# NeoDigito_Mini_V2.net
KiCad netlist of a schematic drawn in EAGLE
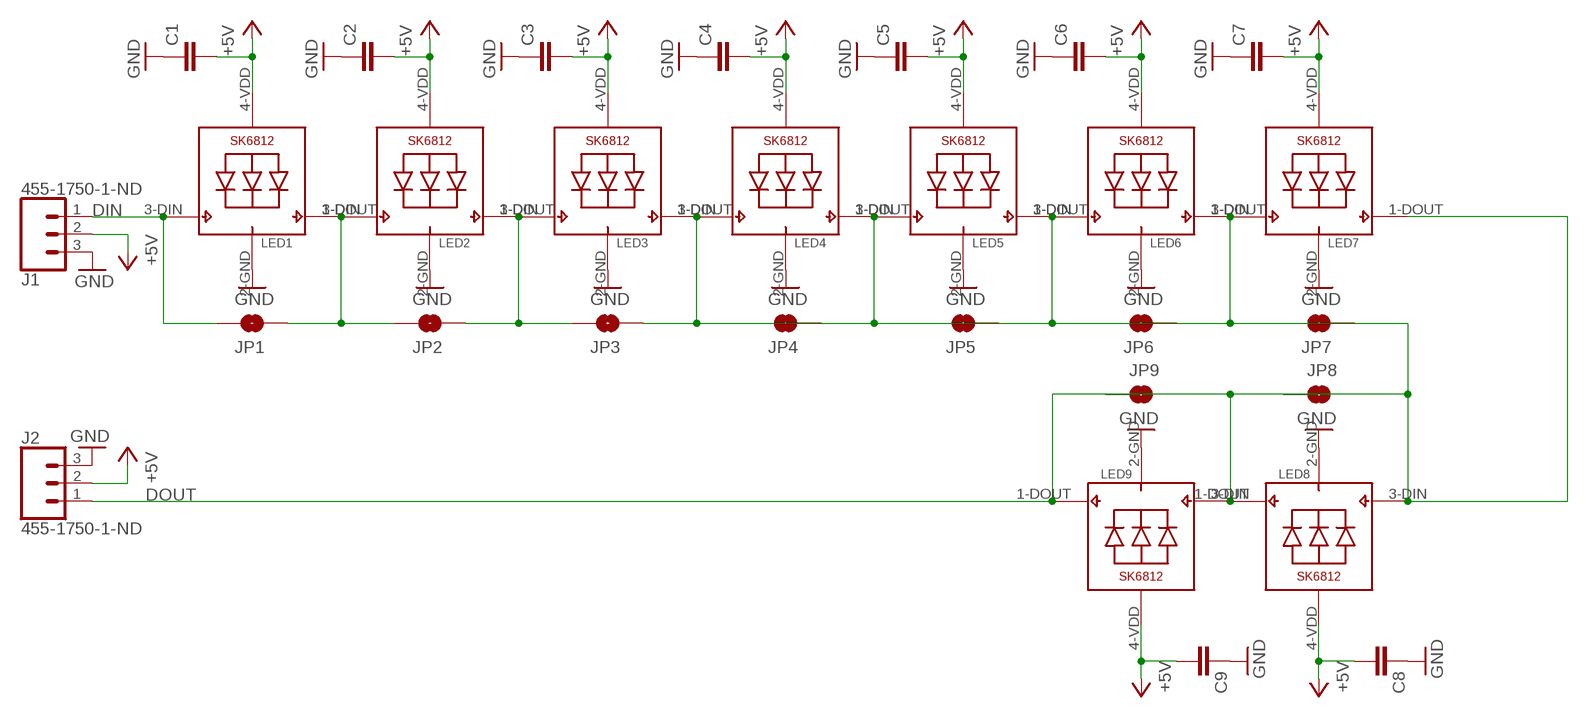
[diagram p0: schematic, sheet 1]

(export (version "E")
  (design (tool "Eeschema 10.0.6"))
  (components
    (comp (ref "C1")
      (value "C-EUC0805")
      (footprint "eagle-import:C0805")
      (libsource (lib "eagle-import") (part "C-EUC0805"))
    )
    (comp (ref "C2")
      (value "C-EUC0805")
      (footprint "eagle-import:C0805")
      (libsource (lib "eagle-import") (part "C-EUC0805"))
    )
    (comp (ref "C3")
      (value "C-EUC0805")
      (footprint "eagle-import:C0805")
      (libsource (lib "eagle-import") (part "C-EUC0805"))
    )
    (comp (ref "C4")
      (value "C-EUC0805")
      (footprint "eagle-import:C0805")
      (libsource (lib "eagle-import") (part "C-EUC0805"))
    )
    (comp (ref "C5")
      (value "C-EUC0805")
      (footprint "eagle-import:C0805")
      (libsource (lib "eagle-import") (part "C-EUC0805"))
    )
    (comp (ref "C6")
      (value "C-EUC0805")
      (footprint "eagle-import:C0805")
      (libsource (lib "eagle-import") (part "C-EUC0805"))
    )
    (comp (ref "C7")
      (value "C-EUC0805")
      (footprint "eagle-import:C0805")
      (libsource (lib "eagle-import") (part "C-EUC0805"))
    )
    (comp (ref "C8")
      (value "C-EUC0805")
      (footprint "eagle-import:C0805")
      (libsource (lib "eagle-import") (part "C-EUC0805"))
    )
    (comp (ref "C9")
      (value "C-EUC0805")
      (footprint "eagle-import:C0805")
      (libsource (lib "eagle-import") (part "C-EUC0805"))
    )
    (comp (ref "J1")
      (value "455-1750-1-ND")
      (footprint "eagle-import:1X03")
      (libsource (lib "eagle-import") (part "CONN_03"))
    )
    (comp (ref "J2")
      (value "455-1750-1-ND")
      (footprint "eagle-import:1X03")
      (libsource (lib "eagle-import") (part "CONN_03"))
    )
    (comp (ref "JP1")
      (value "JUMPER-SMT_2_NO_SILK")
      (footprint "eagle-import:SMT-JUMPER_2_NO_SILK")
      (libsource (lib "eagle-import") (part "JUMPER-SMT_2_NO_SILK"))
    )
    (comp (ref "JP2")
      (value "JUMPER-SMT_2_NO_SILK")
      (footprint "eagle-import:SMT-JUMPER_2_NO_SILK")
      (libsource (lib "eagle-import") (part "JUMPER-SMT_2_NO_SILK"))
    )
    (comp (ref "JP3")
      (value "JUMPER-SMT_2_NO_SILK")
      (footprint "eagle-import:SMT-JUMPER_2_NO_SILK")
      (libsource (lib "eagle-import") (part "JUMPER-SMT_2_NO_SILK"))
    )
    (comp (ref "JP4")
      (value "JUMPER-SMT_2_NO_SILK")
      (footprint "eagle-import:SMT-JUMPER_2_NO_SILK")
      (libsource (lib "eagle-import") (part "JUMPER-SMT_2_NO_SILK"))
    )
    (comp (ref "JP5")
      (value "JUMPER-SMT_2_NO_SILK")
      (footprint "eagle-import:SMT-JUMPER_2_NO_SILK")
      (libsource (lib "eagle-import") (part "JUMPER-SMT_2_NO_SILK"))
    )
    (comp (ref "JP6")
      (value "JUMPER-SMT_2_NO_SILK")
      (footprint "eagle-import:SMT-JUMPER_2_NO_SILK")
      (libsource (lib "eagle-import") (part "JUMPER-SMT_2_NO_SILK"))
    )
    (comp (ref "JP7")
      (value "JUMPER-SMT_2_NO_SILK")
      (footprint "eagle-import:SMT-JUMPER_2_NO_SILK")
      (libsource (lib "eagle-import") (part "JUMPER-SMT_2_NO_SILK"))
    )
    (comp (ref "JP8")
      (value "JUMPER-SMT_2_NO_SILK")
      (footprint "eagle-import:SMT-JUMPER_2_NO_SILK")
      (libsource (lib "eagle-import") (part "JUMPER-SMT_2_NO_SILK"))
    )
    (comp (ref "JP9")
      (value "JUMPER-SMT_2_NO_SILK")
      (footprint "eagle-import:SMT-JUMPER_2_NO_SILK")
      (libsource (lib "eagle-import") (part "JUMPER-SMT_2_NO_SILK"))
    )
    (comp (ref "LED1")
      (value "SK6812_3535")
      (footprint "eagle-import:LED3535")
      (libsource (lib "eagle-import") (part "SK6812_3535"))
    )
    (comp (ref "LED2")
      (value "SK6812_3535")
      (footprint "eagle-import:LED3535")
      (libsource (lib "eagle-import") (part "SK6812_3535"))
    )
    (comp (ref "LED3")
      (value "SK6812_3535")
      (footprint "eagle-import:LED3535")
      (libsource (lib "eagle-import") (part "SK6812_3535"))
    )
    (comp (ref "LED4")
      (value "SK6812_3535")
      (footprint "eagle-import:LED3535")
      (libsource (lib "eagle-import") (part "SK6812_3535"))
    )
    (comp (ref "LED5")
      (value "SK6812_3535")
      (footprint "eagle-import:LED3535")
      (libsource (lib "eagle-import") (part "SK6812_3535"))
    )
    (comp (ref "LED6")
      (value "SK6812_3535")
      (footprint "eagle-import:LED3535")
      (libsource (lib "eagle-import") (part "SK6812_3535"))
    )
    (comp (ref "LED7")
      (value "SK6812_3535")
      (footprint "eagle-import:LED3535")
      (libsource (lib "eagle-import") (part "SK6812_3535"))
    )
    (comp (ref "LED8")
      (value "SK6812_3535")
      (footprint "eagle-import:LED3535")
      (libsource (lib "eagle-import") (part "SK6812_3535"))
    )
    (comp (ref "LED9")
      (value "SK6812_3535")
      (footprint "eagle-import:LED3535")
      (libsource (lib "eagle-import") (part "SK6812_3535"))
    )
  )
  (nets
    (net (code "1") (name "+5V") (class "Default")
      (node (ref "C1") (pin "2") (pinfunction "2_2") (pintype "passive"))
      (node (ref "C2") (pin "2") (pinfunction "2_2") (pintype "passive"))
      (node (ref "C3") (pin "2") (pinfunction "2_2") (pintype "passive"))
      (node (ref "C4") (pin "2") (pinfunction "2_2") (pintype "passive"))
      (node (ref "C5") (pin "2") (pinfunction "2_2") (pintype "passive"))
      (node (ref "C6") (pin "2") (pinfunction "2_2") (pintype "passive"))
      (node (ref "C7") (pin "2") (pinfunction "2_2") (pintype "passive"))
      (node (ref "C8") (pin "2") (pinfunction "2_2") (pintype "passive"))
      (node (ref "C9") (pin "2") (pinfunction "2_2") (pintype "passive"))
      (node (ref "J1") (pin "2") (pinfunction "2_2") (pintype "passive"))
      (node (ref "J2") (pin "2") (pinfunction "2_2") (pintype "passive"))
      (node (ref "LED1") (pin "4-VDD") (pinfunction "VDD_4-VDD") (pintype "power_in"))
      (node (ref "LED2") (pin "4-VDD") (pinfunction "VDD_4-VDD") (pintype "power_in"))
      (node (ref "LED3") (pin "4-VDD") (pinfunction "VDD_4-VDD") (pintype "power_in"))
      (node (ref "LED4") (pin "4-VDD") (pinfunction "VDD_4-VDD") (pintype "power_in"))
      (node (ref "LED5") (pin "4-VDD") (pinfunction "VDD_4-VDD") (pintype "power_in"))
      (node (ref "LED6") (pin "4-VDD") (pinfunction "VDD_4-VDD") (pintype "power_in"))
      (node (ref "LED7") (pin "4-VDD") (pinfunction "VDD_4-VDD") (pintype "power_in"))
      (node (ref "LED8") (pin "4-VDD") (pinfunction "VDD_4-VDD") (pintype "power_in"))
      (node (ref "LED9") (pin "4-VDD") (pinfunction "VDD_4-VDD") (pintype "power_in"))
    )
    (net (code "2") (name "/DIN") (class "Default")
      (node (ref "J1") (pin "1") (pinfunction "1_1") (pintype "passive"))
      (node (ref "JP1") (pin "1") (pinfunction "1_1") (pintype "passive"))
      (node (ref "LED1") (pin "3-DIN") (pinfunction "DI_3-DIN") (pintype "input"))
    )
    (net (code "3") (name "/DOUT") (class "Default")
      (node (ref "J2") (pin "1") (pinfunction "1_1") (pintype "passive"))
      (node (ref "JP9") (pin "1") (pinfunction "1_1") (pintype "passive"))
      (node (ref "LED9") (pin "1-DOUT") (pinfunction "DO_1-DOUT") (pintype "output"))
    )
    (net (code "4") (name "GND") (class "Default")
      (node (ref "C1") (pin "1") (pinfunction "1_1") (pintype "passive"))
      (node (ref "C2") (pin "1") (pinfunction "1_1") (pintype "passive"))
      (node (ref "C3") (pin "1") (pinfunction "1_1") (pintype "passive"))
      (node (ref "C4") (pin "1") (pinfunction "1_1") (pintype "passive"))
      (node (ref "C5") (pin "1") (pinfunction "1_1") (pintype "passive"))
      (node (ref "C6") (pin "1") (pinfunction "1_1") (pintype "passive"))
      (node (ref "C7") (pin "1") (pinfunction "1_1") (pintype "passive"))
      (node (ref "C8") (pin "1") (pinfunction "1_1") (pintype "passive"))
      (node (ref "C9") (pin "1") (pinfunction "1_1") (pintype "passive"))
      (node (ref "J1") (pin "3") (pinfunction "3_3") (pintype "passive"))
      (node (ref "J2") (pin "3") (pinfunction "3_3") (pintype "passive"))
      (node (ref "LED1") (pin "2-GND") (pinfunction "GND_2-GND") (pintype "power_in"))
      (node (ref "LED2") (pin "2-GND") (pinfunction "GND_2-GND") (pintype "power_in"))
      (node (ref "LED3") (pin "2-GND") (pinfunction "GND_2-GND") (pintype "power_in"))
      (node (ref "LED4") (pin "2-GND") (pinfunction "GND_2-GND") (pintype "power_in"))
      (node (ref "LED5") (pin "2-GND") (pinfunction "GND_2-GND") (pintype "power_in"))
      (node (ref "LED6") (pin "2-GND") (pinfunction "GND_2-GND") (pintype "power_in"))
      (node (ref "LED7") (pin "2-GND") (pinfunction "GND_2-GND") (pintype "power_in"))
      (node (ref "LED8") (pin "2-GND") (pinfunction "GND_2-GND") (pintype "power_in"))
      (node (ref "LED9") (pin "2-GND") (pinfunction "GND_2-GND") (pintype "power_in"))
    )
    (net (code "5") (name "Net-(LED1-DO)") (class "Default")
      (node (ref "JP1") (pin "2") (pinfunction "2_2") (pintype "passive"))
      (node (ref "JP2") (pin "1") (pinfunction "1_1") (pintype "passive"))
      (node (ref "LED1") (pin "1-DOUT") (pinfunction "DO_1-DOUT") (pintype "output"))
      (node (ref "LED2") (pin "3-DIN") (pinfunction "DI_3-DIN") (pintype "input"))
    )
    (net (code "6") (name "Net-(LED2-DO)") (class "Default")
      (node (ref "JP2") (pin "2") (pinfunction "2_2") (pintype "passive"))
      (node (ref "JP3") (pin "1") (pinfunction "1_1") (pintype "passive"))
      (node (ref "LED2") (pin "1-DOUT") (pinfunction "DO_1-DOUT") (pintype "output"))
      (node (ref "LED3") (pin "3-DIN") (pinfunction "DI_3-DIN") (pintype "input"))
    )
    (net (code "7") (name "Net-(LED3-DO)") (class "Default")
      (node (ref "JP3") (pin "2") (pinfunction "2_2") (pintype "passive"))
      (node (ref "JP4") (pin "2") (pinfunction "2_2") (pintype "passive"))
      (node (ref "LED3") (pin "1-DOUT") (pinfunction "DO_1-DOUT") (pintype "output"))
      (node (ref "LED4") (pin "3-DIN") (pinfunction "DI_3-DIN") (pintype "input"))
    )
    (net (code "8") (name "Net-(LED4-DO)") (class "Default")
      (node (ref "JP4") (pin "1") (pinfunction "1_1") (pintype "passive"))
      (node (ref "JP5") (pin "2") (pinfunction "2_2") (pintype "passive"))
      (node (ref "LED4") (pin "1-DOUT") (pinfunction "DO_1-DOUT") (pintype "output"))
      (node (ref "LED5") (pin "3-DIN") (pinfunction "DI_3-DIN") (pintype "input"))
    )
    (net (code "9") (name "Net-(LED5-DO)") (class "Default")
      (node (ref "JP5") (pin "1") (pinfunction "1_1") (pintype "passive"))
      (node (ref "JP6") (pin "2") (pinfunction "2_2") (pintype "passive"))
      (node (ref "LED5") (pin "1-DOUT") (pinfunction "DO_1-DOUT") (pintype "output"))
      (node (ref "LED6") (pin "3-DIN") (pinfunction "DI_3-DIN") (pintype "input"))
    )
    (net (code "10") (name "Net-(LED6-DO)") (class "Default")
      (node (ref "JP6") (pin "1") (pinfunction "1_1") (pintype "passive"))
      (node (ref "JP7") (pin "2") (pinfunction "2_2") (pintype "passive"))
      (node (ref "LED6") (pin "1-DOUT") (pinfunction "DO_1-DOUT") (pintype "output"))
      (node (ref "LED7") (pin "3-DIN") (pinfunction "DI_3-DIN") (pintype "input"))
    )
    (net (code "11") (name "Net-(LED7-DO)") (class "Default")
      (node (ref "JP7") (pin "1") (pinfunction "1_1") (pintype "passive"))
      (node (ref "JP8") (pin "2") (pinfunction "2_2") (pintype "passive"))
      (node (ref "LED7") (pin "1-DOUT") (pinfunction "DO_1-DOUT") (pintype "output"))
      (node (ref "LED8") (pin "3-DIN") (pinfunction "DI_3-DIN") (pintype "input"))
    )
    (net (code "12") (name "Net-(LED8-DO)") (class "Default")
      (node (ref "JP8") (pin "1") (pinfunction "1_1") (pintype "passive"))
      (node (ref "JP9") (pin "2") (pinfunction "2_2") (pintype "passive"))
      (node (ref "LED8") (pin "1-DOUT") (pinfunction "DO_1-DOUT") (pintype "output"))
      (node (ref "LED9") (pin "3-DIN") (pinfunction "DI_3-DIN") (pintype "input"))
    )
  )
)
